# SparkFun_Temperatre_Sensor-STTS22H.net
KiCad netlist of a schematic drawn in EAGLE
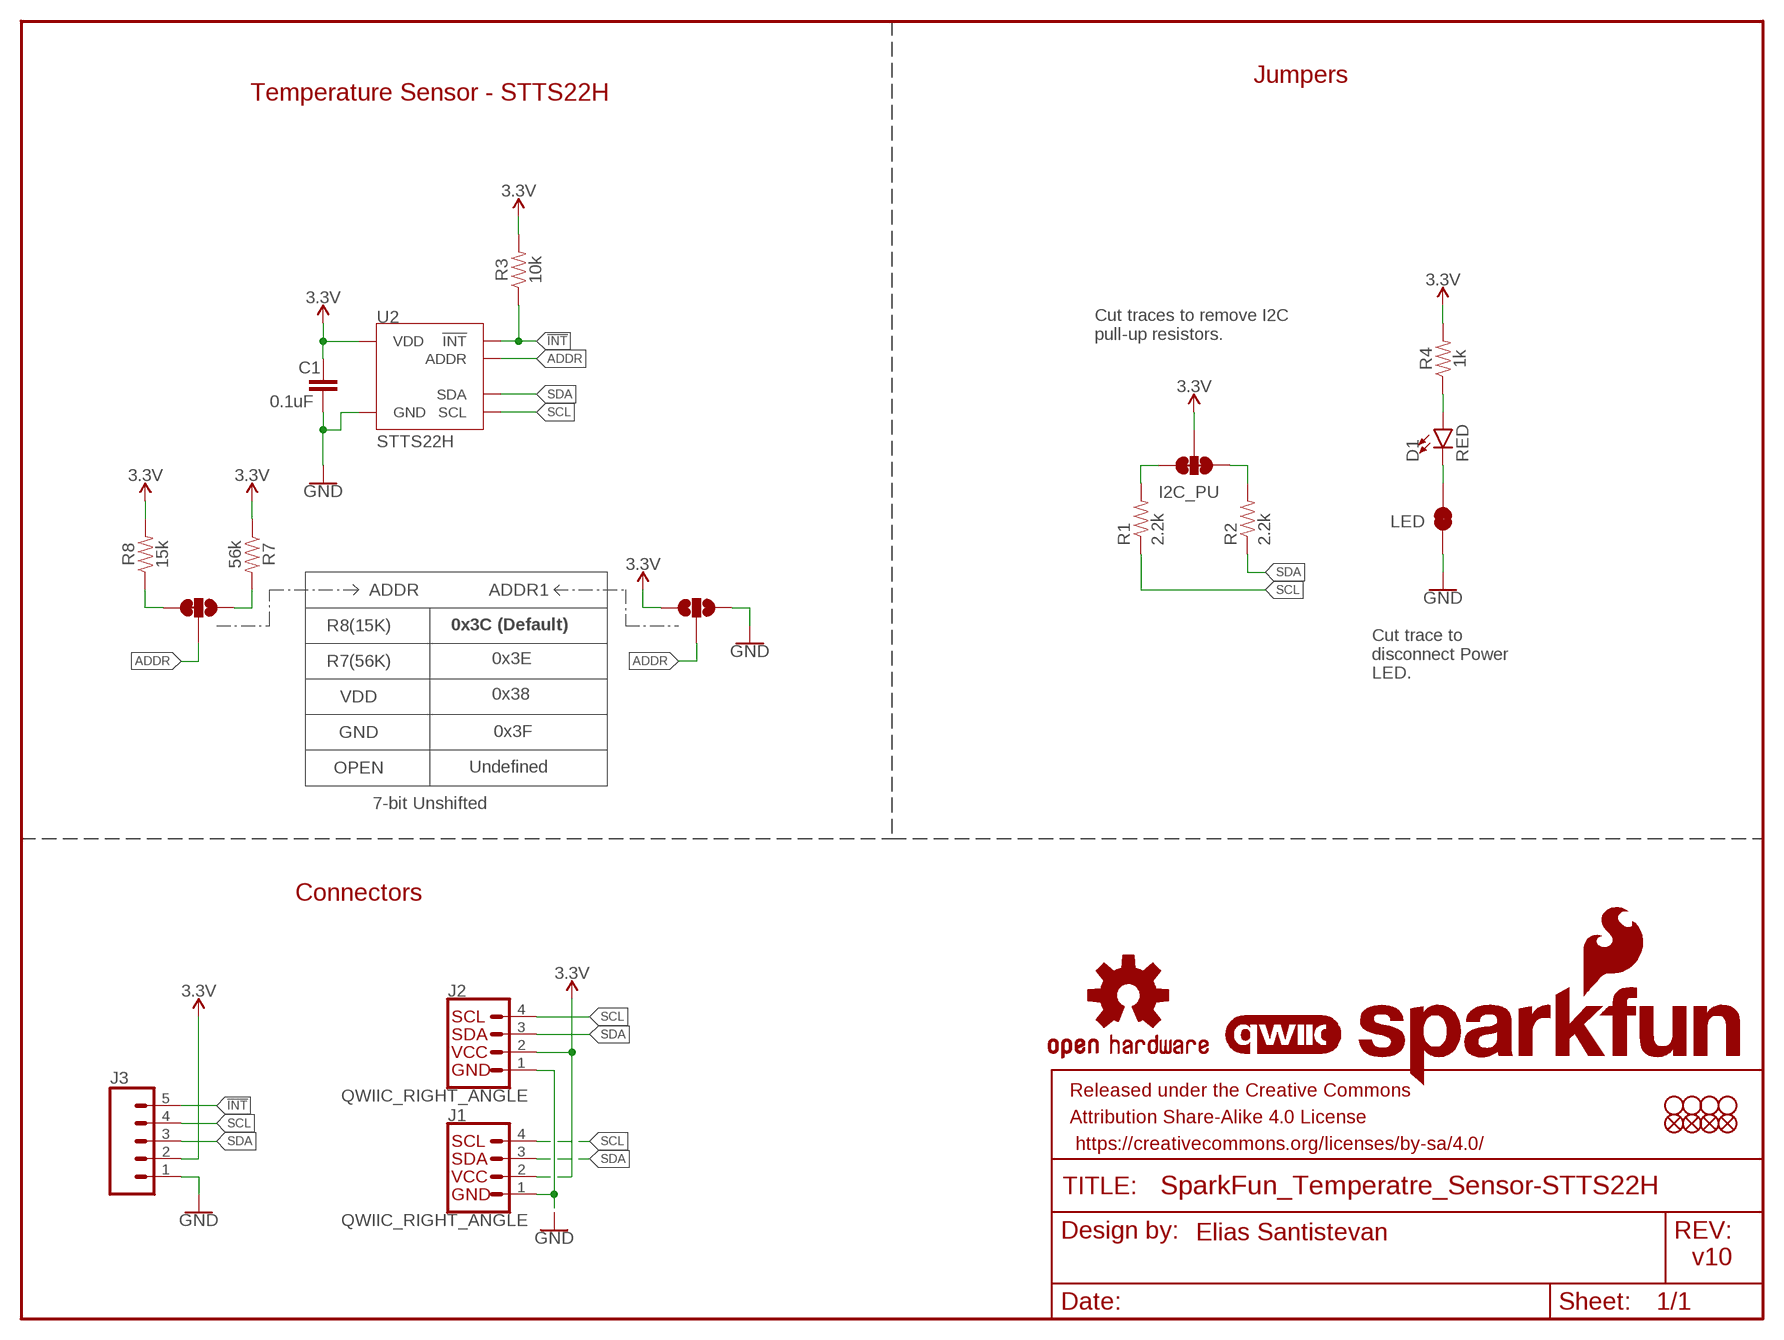
[diagram p0: schematic, sheet 1]

(export (version "E")
  (design (tool "Eeschema 10.0.6"))
  (components
    (comp (ref "ADDR")
      (value "JUMPER-SMT_3_1-NC_TRACE_SILK")
      (footprint "eagle-import:SMT-JUMPER_3_1-NC_TRACE_SILK")
      (libsource (lib "eagle-import") (part "JUMPER-SMT_3_1-NC_TRACE_SILK"))
    )
    (comp (ref "ADDR1")
      (value "JUMPER-SMT_3_NO_SILK")
      (footprint "eagle-import:SMT-JUMPER_3_NO_SILK")
      (libsource (lib "eagle-import") (part "JUMPER-SMT_3_NO_SILK"))
    )
    (comp (ref "C1")
      (value "0.1uF")
      (footprint "eagle-import:0603")
      (libsource (lib "eagle-import") (part "0.1UF-0603-25V-(+80/-20%)"))
    )
    (comp (ref "D1")
      (value "RED")
      (footprint "eagle-import:LED-0603")
      (libsource (lib "eagle-import") (part "LED-RED0603"))
    )
    (comp (ref "FD1")
      (value "FIDUCIAL1X2")
      (footprint "eagle-import:FIDUCIAL-1X2")
      (libsource (lib "eagle-import") (part "FIDUCIAL1X2"))
    )
    (comp (ref "FD2")
      (value "FIDUCIAL1X2")
      (footprint "eagle-import:FIDUCIAL-1X2")
      (libsource (lib "eagle-import") (part "FIDUCIAL1X2"))
    )
    (comp (ref "FD3")
      (value "FIDUCIAL1X2")
      (footprint "eagle-import:FIDUCIAL-1X2")
      (libsource (lib "eagle-import") (part "FIDUCIAL1X2"))
    )
    (comp (ref "FD4")
      (value "FIDUCIAL1X2")
      (footprint "eagle-import:FIDUCIAL-1X2")
      (libsource (lib "eagle-import") (part "FIDUCIAL1X2"))
    )
    (comp (ref "FRAME1")
      (value "FRAME-LETTER")
      (footprint "eagle-import:CREATIVE_COMMONS")
      (fields (field (name "DESIGNER") "Elias Santistevan"))
      (libsource (lib "eagle-import") (part "FRAME-LETTER"))
    )
    (comp (ref "I2C_PU")
      (value "S_MODE")
      (footprint "eagle-import:SMT-JUMPER_3_2-NC_TRACE_SILK")
      (libsource (lib "eagle-import") (part "JUMPER-SMT_3_2-NC_TRACE_SILK"))
    )
    (comp (ref "J1")
      (value "QWIIC_RIGHT_ANGLE")
      (footprint "eagle-import:JST04_1MM_RA")
      (libsource (lib "eagle-import") (part "QWIIC_CONNECTORJS-1MM"))
    )
    (comp (ref "J2")
      (value "QWIIC_RIGHT_ANGLE")
      (footprint "eagle-import:JST04_1MM_RA")
      (libsource (lib "eagle-import") (part "QWIIC_CONNECTORJS-1MM"))
    )
    (comp (ref "J3")
      (value "CONN_05NO_SILK")
      (footprint "eagle-import:1X05_NO_SILK")
      (libsource (lib "eagle-import") (part "CONN_05NO_SILK"))
    )
    (comp (ref "LED")
      (value "JUMPER-SMT_2_NC_TRACE_SILK")
      (footprint "eagle-import:SMT-JUMPER_2_NC_TRACE_SILK")
      (libsource (lib "eagle-import") (part "JUMPER-SMT_2_NC_TRACE_SILK"))
    )
    (comp (ref "LOGO2")
      (value "OSHW-LOGOMINI")
      (footprint "eagle-import:OSHW-LOGO-MINI")
      (libsource (lib "eagle-import") (part "OSHW-LOGOMINI"))
    )
    (comp (ref "LOGO3")
      (value "SFE_LOGO_NAME_FLAME.1_INCH")
      (footprint "eagle-import:SFE_LOGO_NAME_FLAME_.1")
      (libsource (lib "eagle-import") (part "SFE_LOGO_NAME_FLAME.1_INCH"))
    )
    (comp (ref "LOGO4")
      (value "QWIIC_LOGO_4MM")
      (footprint "eagle-import:QWIIC_4MM")
      (libsource (lib "eagle-import") (part "QWIIC_LOGO_4MM"))
    )
    (comp (ref "R1")
      (value "2.2k")
      (footprint "eagle-import:0603")
      (libsource (lib "eagle-import") (part "2.2KOHM-0603-1/10W-1%"))
    )
    (comp (ref "R2")
      (value "2.2k")
      (footprint "eagle-import:0603")
      (libsource (lib "eagle-import") (part "2.2KOHM-0603-1/10W-1%"))
    )
    (comp (ref "R3")
      (value "10k")
      (footprint "eagle-import:0603")
      (libsource (lib "eagle-import") (part "10KOHM-0603-1/10W-1%"))
    )
    (comp (ref "R4")
      (value "1k")
      (footprint "eagle-import:0603")
      (libsource (lib "eagle-import") (part "1KOHM-0603-1/10W-1%"))
    )
    (comp (ref "R7")
      (value "56k")
      (footprint "eagle-import:0603")
      (libsource (lib "eagle-import") (part "56KOHM"))
    )
    (comp (ref "R8")
      (value "15k")
      (footprint "eagle-import:0603")
      (libsource (lib "eagle-import") (part "15KOHM-0603-1/10W-1%"))
    )
    (comp (ref "STANDOFF1")
      (value "STAND-OFFTIGHT")
      (footprint "eagle-import:STAND-OFF-TIGHT")
      (libsource (lib "eagle-import") (part "STAND-OFFTIGHT"))
    )
    (comp (ref "STANDOFF2")
      (value "STAND-OFFTIGHT")
      (footprint "eagle-import:STAND-OFF-TIGHT")
      (libsource (lib "eagle-import") (part "STAND-OFFTIGHT"))
    )
    (comp (ref "STANDOFF3")
      (value "STAND-OFFTIGHT")
      (footprint "eagle-import:STAND-OFF-TIGHT")
      (libsource (lib "eagle-import") (part "STAND-OFFTIGHT"))
    )
    (comp (ref "STANDOFF5")
      (value "STAND-OFFTIGHT")
      (footprint "eagle-import:STAND-OFF-TIGHT")
      (libsource (lib "eagle-import") (part "STAND-OFFTIGHT"))
    )
    (comp (ref "U2")
      (value "STTS22H")
      (footprint "eagle-import:UDFN-6L")
      (libsource (lib "eagle-import") (part "STTS22H"))
    )
  )
  (nets
    (net (code "1") (name "/~{INT}") (class "Default")
      (node (ref "J3") (pin "5") (pinfunction "5_5") (pintype "passive"))
      (node (ref "R3") (pin "1") (pinfunction "1_1") (pintype "passive"))
      (node (ref "U2") (pin "P2") (pinfunction "~{INT}_P2") (pintype "bidirectional"))
    )
    (net (code "2") (name "3.3V") (class "Default")
      (node (ref "ADDR1") (pin "3") (pinfunction "3_3") (pintype "passive"))
      (node (ref "C1") (pin "1") (pinfunction "1_1") (pintype "passive"))
      (node (ref "I2C_PU") (pin "2") (pinfunction "2_2") (pintype "passive"))
      (node (ref "J1") (pin "2") (pinfunction "2_2") (pintype "power_in"))
      (node (ref "J2") (pin "2") (pinfunction "2_2") (pintype "power_in"))
      (node (ref "J3") (pin "2") (pinfunction "2_2") (pintype "passive"))
      (node (ref "R3") (pin "2") (pinfunction "2_2") (pintype "passive"))
      (node (ref "R4") (pin "2") (pinfunction "2_2") (pintype "passive"))
      (node (ref "R7") (pin "1") (pinfunction "1_1") (pintype "passive"))
      (node (ref "R8") (pin "2") (pinfunction "2_2") (pintype "passive"))
      (node (ref "U2") (pin "P3") (pinfunction "VDD_P3") (pintype "power_in"))
    )
    (net (code "3") (name "ADDR") (class "Default")
      (node (ref "ADDR") (pin "2") (pinfunction "2_2") (pintype "passive"))
      (node (ref "ADDR1") (pin "2") (pinfunction "2_2") (pintype "passive"))
      (node (ref "U2") (pin "P4") (pinfunction "ADDR_P4") (pintype "bidirectional"))
    )
    (net (code "4") (name "GND") (class "Default")
      (node (ref "ADDR1") (pin "1") (pinfunction "1_1") (pintype "passive"))
      (node (ref "C1") (pin "2") (pinfunction "2_2") (pintype "passive"))
      (node (ref "J1") (pin "1") (pinfunction "1_1") (pintype "power_in"))
      (node (ref "J2") (pin "1") (pinfunction "1_1") (pintype "power_in"))
      (node (ref "J3") (pin "1") (pinfunction "1_1") (pintype "passive"))
      (node (ref "LED") (pin "1") (pinfunction "1_1") (pintype "passive"))
      (node (ref "U2") (pin "P5") (pinfunction "GND_P5") (pintype "power_in"))
      (node (ref "U2") (pin "P7") (pinfunction "GND_P7") (pintype "power_in"))
    )
    (net (code "5") (name "Net-(ADDR-Pad1)") (class "Default")
      (node (ref "ADDR") (pin "1") (pinfunction "1_1") (pintype "passive"))
      (node (ref "R7") (pin "2") (pinfunction "2_2") (pintype "passive"))
    )
    (net (code "6") (name "Net-(ADDR-Pad3)") (class "Default")
      (node (ref "ADDR") (pin "3") (pinfunction "3_3") (pintype "passive"))
      (node (ref "R8") (pin "1") (pinfunction "1_1") (pintype "passive"))
    )
    (net (code "7") (name "Net-(D1-PadA)") (class "Default")
      (node (ref "D1") (pin "A") (pinfunction "A_A") (pintype "passive"))
      (node (ref "R4") (pin "1") (pinfunction "1_1") (pintype "passive"))
    )
    (net (code "8") (name "Net-(D1-PadC)") (class "Default")
      (node (ref "D1") (pin "C") (pinfunction "C_C") (pintype "passive"))
      (node (ref "LED") (pin "2") (pinfunction "2_2") (pintype "passive"))
    )
    (net (code "9") (name "Net-(I2C_PU-Pad1)") (class "Default")
      (node (ref "I2C_PU") (pin "1") (pinfunction "1_1") (pintype "passive"))
      (node (ref "R1") (pin "2") (pinfunction "2_2") (pintype "passive"))
    )
    (net (code "10") (name "Net-(I2C_PU-Pad3)") (class "Default")
      (node (ref "I2C_PU") (pin "3") (pinfunction "3_3") (pintype "passive"))
      (node (ref "R2") (pin "2") (pinfunction "2_2") (pintype "passive"))
    )
    (net (code "11") (name "SCL") (class "Default")
      (node (ref "J1") (pin "4") (pinfunction "4_4") (pintype "passive"))
      (node (ref "J2") (pin "4") (pinfunction "4_4") (pintype "passive"))
      (node (ref "J3") (pin "4") (pinfunction "4_4") (pintype "passive"))
      (node (ref "R1") (pin "1") (pinfunction "1_1") (pintype "passive"))
      (node (ref "U2") (pin "P1") (pinfunction "SCL_P1") (pintype "bidirectional"))
    )
    (net (code "12") (name "SDA") (class "Default")
      (node (ref "J1") (pin "3") (pinfunction "3_3") (pintype "passive"))
      (node (ref "J2") (pin "3") (pinfunction "3_3") (pintype "passive"))
      (node (ref "J3") (pin "3") (pinfunction "3_3") (pintype "passive"))
      (node (ref "R2") (pin "1") (pinfunction "1_1") (pintype "passive"))
      (node (ref "U2") (pin "P6") (pinfunction "SDA_P6") (pintype "bidirectional"))
    )
  )
)
